# mcu_and_input_power.net
KiCad netlist of a schematic drawn in Altium Designer
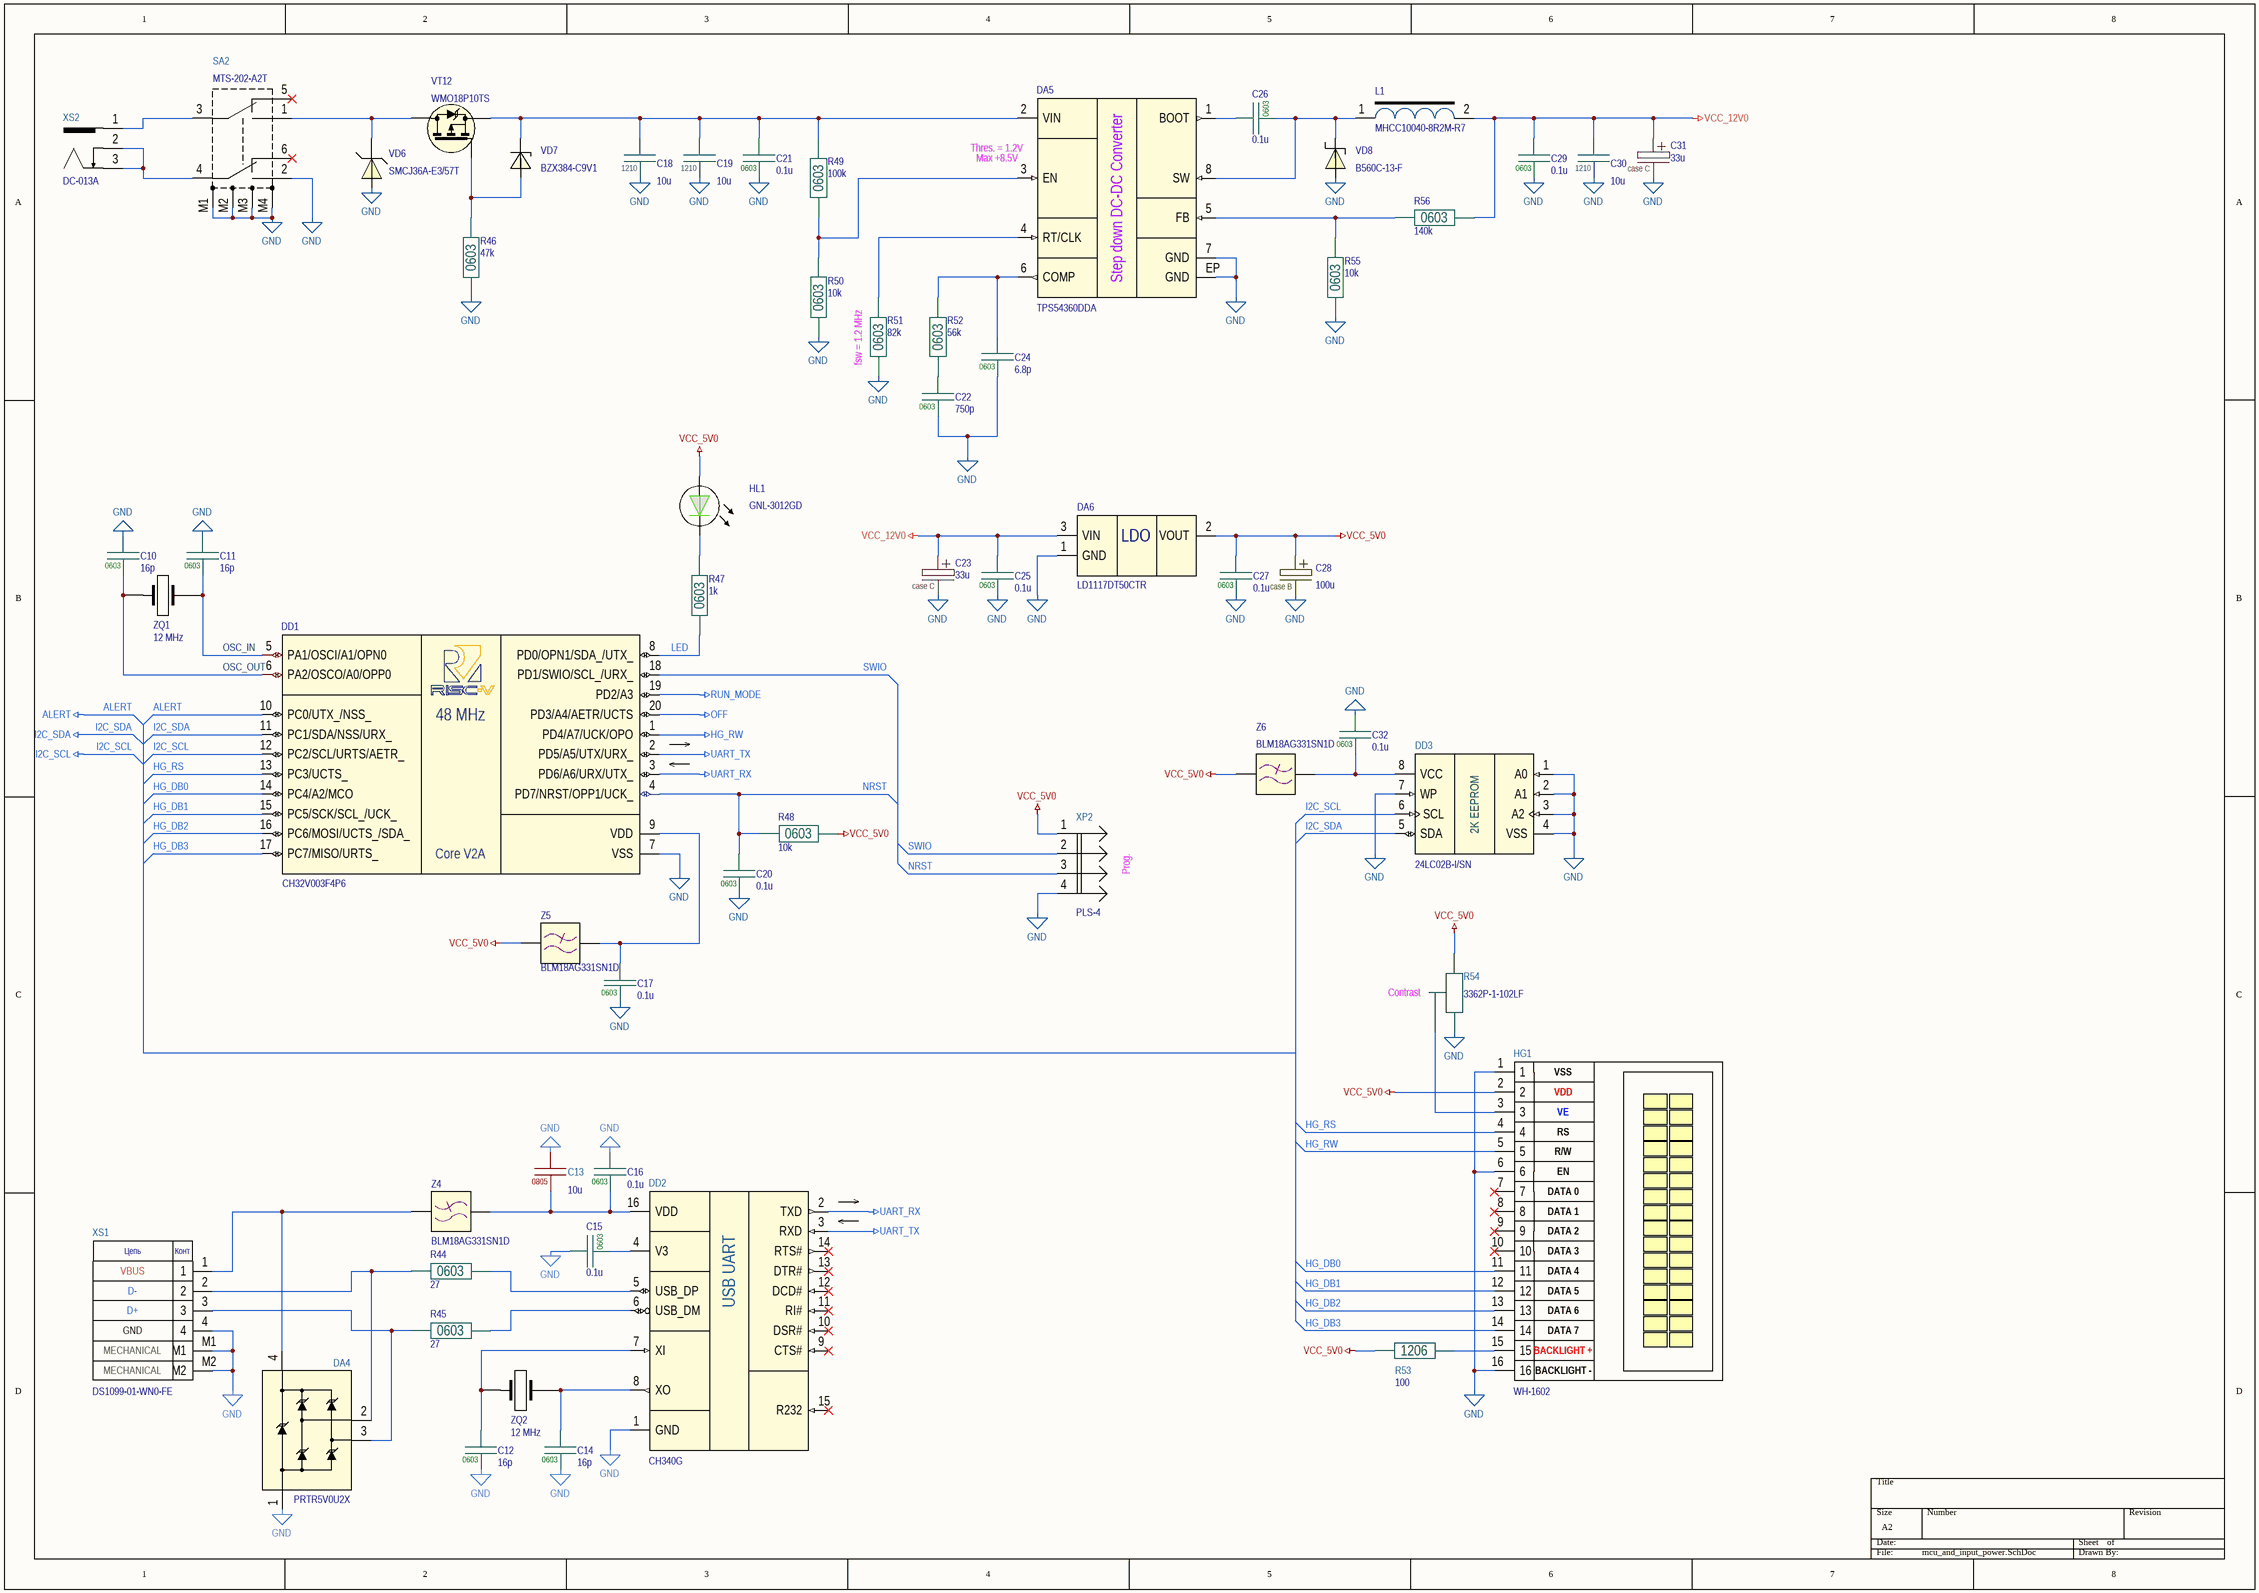
[diagram p0: mcu_and_input_power.SchDoc]

(export (version "E")
  (design (tool "Eeschema 10.0.6"))
  (components
    (comp (ref "C10")
      (value "16p")
      (footprint "PcbLib_RC:CAP0603")
      (description "Capacitors 0603 package case")
      (fields
        (field (name "TOLERANCE") "± 5 %")
        (field (name "VOLTAGE") "50V")
        (field (name "PACKAGE") "0603")
      )
      (libsource (lib "Schlib_RC") (part "C0603"))
    )
    (comp (ref "C11")
      (value "16p")
      (footprint "PcbLib_RC:CAP0603")
      (description "Capacitors 0603 package case")
      (fields
        (field (name "TOLERANCE") "± 5 %")
        (field (name "VOLTAGE") "50V")
        (field (name "PACKAGE") "0603")
      )
      (libsource (lib "Schlib_RC") (part "C0603"))
    )
    (comp (ref "C12")
      (value "16p")
      (footprint "PcbLib_RC:CAP0603")
      (description "Capacitors 0603 package case")
      (fields
        (field (name "TOLERANCE") "± 5 %")
        (field (name "VOLTAGE") "50V")
        (field (name "PACKAGE") "0603")
      )
      (libsource (lib "Schlib_RC") (part "C0603"))
    )
    (comp (ref "C13")
      (value "10u")
      (footprint "PcbLib_RC:CAP0805-0.75")
      (description "Capacitors 0805 package case")
      (fields
        (field (name "TOLERANCE") "± 10 %")
        (field (name "VOLTAGE") "16V")
        (field (name "PACKAGE") "0805")
      )
      (libsource (lib "Schlib_RC") (part "C0805"))
    )
    (comp (ref "C14")
      (value "16p")
      (footprint "PcbLib_RC:CAP0603")
      (description "Capacitors 0603 package case")
      (fields
        (field (name "TOLERANCE") "± 5 %")
        (field (name "VOLTAGE") "50V")
        (field (name "PACKAGE") "0603")
      )
      (libsource (lib "Schlib_RC") (part "C0603"))
    )
    (comp (ref "C15")
      (value "0.1u")
      (footprint "PcbLib_RC:CAP0603")
      (description "Capacitors 0603 package case")
      (fields
        (field (name "TOLERANCE") "± 10 %")
        (field (name "VOLTAGE") "50V")
        (field (name "PACKAGE") "0603")
      )
      (libsource (lib "Schlib_RC") (part "C0603"))
    )
    (comp (ref "C16")
      (value "0.1u")
      (footprint "PcbLib_RC:CAP0603")
      (description "Capacitors 0603 package case")
      (fields
        (field (name "TOLERANCE") "± 10 %")
        (field (name "VOLTAGE") "50V")
        (field (name "PACKAGE") "0603")
      )
      (libsource (lib "Schlib_RC") (part "C0603"))
    )
    (comp (ref "C17")
      (value "0.1u")
      (footprint "PcbLib_RC:CAP0603")
      (description "Capacitors 0603 package case")
      (fields
        (field (name "TOLERANCE") "± 10 %")
        (field (name "VOLTAGE") "50V")
        (field (name "PACKAGE") "0603")
      )
      (libsource (lib "Schlib_RC") (part "C0603"))
    )
    (comp (ref "C18")
      (value "10u")
      (footprint "PcbLib_RC:CAP1210-2.2")
      (description "Capacitors 1210 package case")
      (fields
        (field (name "TOLERANCE") "± 10 %")
        (field (name "VOLTAGE") "100V")
        (field (name "PACKAGE") "1210")
      )
      (libsource (lib "Schlib_RC") (part "C1210"))
    )
    (comp (ref "C19")
      (value "10u")
      (footprint "PcbLib_RC:CAP1210-2.2")
      (description "Capacitors 1210 package case")
      (fields
        (field (name "TOLERANCE") "± 10 %")
        (field (name "VOLTAGE") "100V")
        (field (name "PACKAGE") "1210")
      )
      (libsource (lib "Schlib_RC") (part "C1210"))
    )
    (comp (ref "C20")
      (value "0.1u")
      (footprint "PcbLib_RC:CAP0603")
      (description "Capacitors 0603 package case")
      (fields
        (field (name "TOLERANCE") "± 10 %")
        (field (name "VOLTAGE") "50V")
        (field (name "PACKAGE") "0603")
      )
      (libsource (lib "Schlib_RC") (part "C0603"))
    )
    (comp (ref "C21")
      (value "0.1u")
      (footprint "PcbLib_RC:CAP0603")
      (description "Capacitors 0603 package case")
      (fields
        (field (name "TOLERANCE") "± 10 %")
        (field (name "VOLTAGE") "50V")
        (field (name "PACKAGE") "0603")
      )
      (libsource (lib "Schlib_RC") (part "C0603"))
    )
    (comp (ref "C22")
      (value "750p")
      (footprint "PcbLib_RC:CAP0603")
      (description "Capacitors 0603 package case")
      (fields
        (field (name "TOLERANCE") "± 5 %")
        (field (name "VOLTAGE") "50V")
        (field (name "PACKAGE") "0603")
      )
      (libsource (lib "Schlib_RC") (part "C0603"))
    )
    (comp (ref "C23")
      (value "33u")
      (footprint "PcbLib_RC:CAP_CASE_C")
      (description "Tantalum capacitors case C")
      (fields
        (field (name "TOLERANCE") "± 10 %")
        (field (name "PART NUMBER") "293D336X9020C2TE3")
        (field (name "PACKAGE") "case C")
      )
      (libsource (lib "Schlib_RC") (part "C_CASEC"))
    )
    (comp (ref "C24")
      (value "6.8p")
      (footprint "PcbLib_RC:CAP0603")
      (description "Capacitors 0603 package case")
      (fields
        (field (name "TOLERANCE") "± 0.25 pF")
        (field (name "VOLTAGE") "50V")
        (field (name "PACKAGE") "0603")
      )
      (libsource (lib "Schlib_RC") (part "C0603"))
    )
    (comp (ref "C25")
      (value "0.1u")
      (footprint "PcbLib_RC:CAP0603")
      (description "Capacitors 0603 package case")
      (fields
        (field (name "TOLERANCE") "± 10 %")
        (field (name "VOLTAGE") "50V")
        (field (name "PACKAGE") "0603")
      )
      (libsource (lib "Schlib_RC") (part "C0603"))
    )
    (comp (ref "C26")
      (value "0.1u")
      (footprint "PcbLib_RC:CAP0603")
      (description "Capacitors 0603 package case")
      (fields
        (field (name "TOLERANCE") "± 10 %")
        (field (name "VOLTAGE") "50V")
        (field (name "PACKAGE") "0603")
      )
      (libsource (lib "Schlib_RC") (part "C0603"))
    )
    (comp (ref "C27")
      (value "0.1u")
      (footprint "PcbLib_RC:CAP0603")
      (description "Capacitors 0603 package case")
      (fields
        (field (name "TOLERANCE") "± 10 %")
        (field (name "VOLTAGE") "50V")
        (field (name "PACKAGE") "0603")
      )
      (libsource (lib "Schlib_RC") (part "C0603"))
    )
    (comp (ref "C28")
      (value "100u")
      (footprint "PcbLib_RC:CAP_CASE_B")
      (description "Tantalum capacitors case B")
      (fields
        (field (name "TOLERANCE") "± 10 %")
        (field (name "PART NUMBER") "293D107X0010B2TE3")
        (field (name "PACKAGE") "case B")
      )
      (libsource (lib "Schlib_RC") (part "C_CASEB"))
    )
    (comp (ref "C29")
      (value "0.1u")
      (footprint "PcbLib_RC:CAP0603")
      (description "Capacitors 0603 package case")
      (fields
        (field (name "TOLERANCE") "± 10 %")
        (field (name "VOLTAGE") "50V")
        (field (name "PACKAGE") "0603")
      )
      (libsource (lib "Schlib_RC") (part "C0603"))
    )
    (comp (ref "C30")
      (value "10u")
      (footprint "PcbLib_RC:CAP1210-2.2")
      (description "Capacitors 1210 package case")
      (fields
        (field (name "TOLERANCE") "± 10 %")
        (field (name "VOLTAGE") "100V")
        (field (name "PACKAGE") "1210")
      )
      (libsource (lib "Schlib_RC") (part "C1210"))
    )
    (comp (ref "C31")
      (value "33u")
      (footprint "PcbLib_RC:CAP_CASE_C")
      (description "Tantalum capacitors case C")
      (fields
        (field (name "TOLERANCE") "± 10 %")
        (field (name "PART NUMBER") "293D336X9020C2TE3")
        (field (name "PACKAGE") "case C")
      )
      (libsource (lib "Schlib_RC") (part "C_CASEC"))
    )
    (comp (ref "C32")
      (value "0.1u")
      (footprint "PcbLib_RC:CAP0603")
      (description "Capacitors 0603 package case")
      (fields
        (field (name "TOLERANCE") "± 10 %")
        (field (name "VOLTAGE") "50V")
        (field (name "PACKAGE") "0603")
      )
      (libsource (lib "Schlib_RC") (part "C0603"))
    )
    (comp (ref "DA4")
      (value "PRTR5V0U2X")
      (footprint "PcbLib_ICs:SOT143")
      (description "Ultra low capacitance double rail-to-rail ESD protection diode")
      (fields (field (name "MANUFACTURER") "NXP USA Inc."))
      (libsource (lib "Schlib_NXP_Semiconductors") (part "PRTR5V0U2X"))
    )
    (comp (ref "DA5")
      (value "TPS54360DDA")
      (footprint "PcbLib_ICs:SOIC-8EP")
      (description "60-V Input, 3.5-A, Step-Down DC/DC Converter With Eco-Mode")
      (fields (field (name "MANUFACTURER") "Texas Instruments"))
      (libsource (lib "Schlib_Texas_Instruments") (part "TPS54360DDA"))
    )
    (comp (ref "DA6")
      (value "LD1117DT50CTR")
      (footprint "PcbLib_ICs:TO-252-3")
      (description "Low drop positive voltage regulator")
      (fields (field (name "MANUFACTURER") "STMicroelectronics"))
      (libsource (lib "Schlib_STMicroelectronics") (part "LD1117DT50CTR"))
    )
    (comp (ref "DD1")
      (value "CH32V003F4P6")
      (footprint "PcbLib_ICs:TSSOP-20")
      (description "RISC-V MCU 48MHz with 16KB flash, 2KB RAM")
      (fields (field (name "MANUFACTURER") "WinChipHead"))
      (libsource (lib "Schlib_WCH") (part "CH32V003F4P6"))
    )
    (comp (ref "DD2")
      (value "CH340G")
      (footprint "PcbLib_ICs:SOIC-16")
      (description "USB to Serial Port Chip")
      (fields (field (name "MANUFACTURER") "WinChipHead"))
      (libsource (lib "Schlib_WCH") (part "CH340G"))
    )
    (comp (ref "DD3")
      (value "24LC02B-I/SN")
      (footprint "PcbLib_ICs:SOIC-8")
      (description "2K I2C Serial EEPROM")
      (fields (field (name "MANUFACTURER") "Microchip Technology"))
      (libsource (lib "Schlib_Microchip") (part "24LC02B-I/SN"))
    )
    (comp (ref "HG1")
      (value "WH-1602")
      (footprint "PcbLib_Others:WH1602")
      (description "1602 Display with 16 pin PBS connector")
      (libsource (lib "Schlib_OtherComponents") (part "WH-1602"))
    )
    (comp (ref "HL1")
      (value "GNL-3012GD")
      (footprint "PcbLib_Discrete:GNL-3012GD")
      (description "Standard Brightness 3mm LED")
      (fields (field (name "MANUFACTURER") "G-Nor Optoelectronics"))
      (libsource (lib "Schlib_OtherComponents") (part "GNL-3012GD"))
    )
    (comp (ref "L1")
      (value "MHCC10040-8R2M-R7")
      (footprint "PcbLib_RC:MHCC10040")
      (description "Shielded SMD Power Inductor")
      (fields (field (name "MANUFACTURER") "Chilisin Elec"))
      (libsource (lib "Schlib_OtherComponents") (part "MHCC10040-8R2M-R7"))
    )
    (comp (ref "R44")
      (value "27")
      (footprint "PcbLib_RC:RES0603B")
      (description "Resistor 0603 package case")
      (fields
        (field (name "TOLERANCE") "± 1 %")
        (field (name "PART NUMBER") "RC0603FR-0727RL")
        (field (name "PACKAGE") "0603")
      )
      (libsource (lib "Schlib_RC") (part "R0603"))
    )
    (comp (ref "R45")
      (value "27")
      (footprint "PcbLib_RC:RES0603B")
      (description "Resistor 0603 package case")
      (fields
        (field (name "TOLERANCE") "± 1 %")
        (field (name "PART NUMBER") "RC0603FR-0727RL")
        (field (name "PACKAGE") "0603")
      )
      (libsource (lib "Schlib_RC") (part "R0603"))
    )
    (comp (ref "R46")
      (value "47k")
      (footprint "PcbLib_RC:RES0603B")
      (description "Resistor 0603 package case")
      (fields
        (field (name "TOLERANCE") "± 1 %")
        (field (name "PART NUMBER") "RC0603FR-0747KL")
        (field (name "PACKAGE") "0603")
      )
      (libsource (lib "Schlib_RC") (part "R0603"))
    )
    (comp (ref "R47")
      (value "1k")
      (footprint "PcbLib_RC:RES0603B")
      (description "Resistor 0603 package case")
      (fields
        (field (name "TOLERANCE") "± 1 %")
        (field (name "PART NUMBER") "RC0603FR-071KL")
        (field (name "PACKAGE") "0603")
      )
      (libsource (lib "Schlib_RC") (part "R0603"))
    )
    (comp (ref "R48")
      (value "10k")
      (footprint "PcbLib_RC:RES0603B")
      (description "Resistor 0603 package case")
      (fields
        (field (name "TOLERANCE") "± 1 %")
        (field (name "PART NUMBER") "RC0603FR-0710KL")
        (field (name "PACKAGE") "0603")
      )
      (libsource (lib "Schlib_RC") (part "R0603"))
    )
    (comp (ref "R49")
      (value "100k")
      (footprint "PcbLib_RC:RES0603B")
      (description "Resistor 0603 package case")
      (fields
        (field (name "TOLERANCE") "± 1 %")
        (field (name "PART NUMBER") "RC0603FR-07100KL")
        (field (name "PACKAGE") "0603")
      )
      (libsource (lib "Schlib_RC") (part "R0603"))
    )
    (comp (ref "R50")
      (value "10k")
      (footprint "PcbLib_RC:RES0603B")
      (description "Resistor 0603 package case")
      (fields
        (field (name "TOLERANCE") "± 1 %")
        (field (name "PART NUMBER") "RC0603FR-0710KL")
        (field (name "PACKAGE") "0603")
      )
      (libsource (lib "Schlib_RC") (part "R0603"))
    )
    (comp (ref "R51")
      (value "82k")
      (footprint "PcbLib_RC:RES0603B")
      (description "Resistor 0603 package case")
      (fields
        (field (name "TOLERANCE") "± 1 %")
        (field (name "PART NUMBER") "RC0603FR-0782KL")
        (field (name "PACKAGE") "0603")
      )
      (libsource (lib "Schlib_RC") (part "R0603"))
    )
    (comp (ref "R52")
      (value "56k")
      (footprint "PcbLib_RC:RES0603B")
      (description "Resistor 0603 package case")
      (fields
        (field (name "TOLERANCE") "± 1 %")
        (field (name "PART NUMBER") "RC0603FR-0756KL")
        (field (name "PACKAGE") "0603")
      )
      (libsource (lib "Schlib_RC") (part "R0603"))
    )
    (comp (ref "R53")
      (value "100")
      (footprint "PcbLib_RC:RES1206C")
      (description "Resistor 1206 package case")
      (fields
        (field (name "TOLERANCE") "± 1 %")
        (field (name "MANUFACTURER") "Yageo")
        (field (name "PACKAGE") "1206")
      )
      (libsource (lib "Schlib_RC") (part "R1206"))
    )
    (comp (ref "R54")
      (value "3362P-1-102LF")
      (footprint "PcbLib_Others:3362P")
      (description "TRIMMER 1K OHM 0.5W PC PIN TOP")
      (fields (field (name "MANUFACTURER") "Bourns Inc."))
      (libsource (lib "Schlib_Bourns") (part "3362P-1-102LF"))
    )
    (comp (ref "R55")
      (value "10k")
      (footprint "PcbLib_RC:RES0603B")
      (description "Resistor 0603 package case")
      (fields
        (field (name "TOLERANCE") "± 1 %")
        (field (name "PART NUMBER") "RC0603FR-0710KL")
        (field (name "PACKAGE") "0603")
      )
      (libsource (lib "Schlib_RC") (part "R0603"))
    )
    (comp (ref "R56")
      (value "140k")
      (footprint "PcbLib_RC:RES0603B")
      (description "Resistor 0603 package case")
      (fields
        (field (name "TOLERANCE") "± 1 %")
        (field (name "PART NUMBER") "RC0603FR-07140KL")
        (field (name "PACKAGE") "0603")
      )
      (libsource (lib "Schlib_RC") (part "R0603"))
    )
    (comp (ref "SA2")
      (value "MTS-202-A2T")
      (footprint "PcbLib_Others:MTS-202-A2T")
      (description "Switch")
      (fields (field (name "MANUFACTURER") "RUICHI"))
      (libsource (lib "Schlib_OtherComponents") (part "MTS-202-A2T"))
    )
    (comp (ref "VD6")
      (value "SMCJ36A-E3/57T")
      (footprint "PcbLib_Discrete:DO-214AB")
      (description "36V Transient Voltage Suppressors")
      (fields (field (name "MANUFACTURER") "Vishay"))
      (libsource (lib "Schlib_Vishay") (part "SMCJ36A-E3/57T"))
    )
    (comp (ref "VD7")
      (value "BZX384-C9V1")
      (footprint "PcbLib_Discrete:SOD-323")
      (description "Voltage regulator diodes 9.1V")
      (libsource (lib "Schlib_NXP_Semiconductors") (part "BZX384-C9V1"))
    )
    (comp (ref "VD8")
      (value "B560C-13-F")
      (footprint "PcbLib_Discrete:DO-214AB")
      (description "Diode Schottky 60V, 5A")
      (fields (field (name "MANUFACTURER") "Diodes Incorporated"))
      (libsource (lib "Schlib_Diodes_Incorporated") (part "B560C-13-F"))
    )
    (comp (ref "VT12")
      (value "WMO18P10TS")
      (footprint "PcbLib_ICs:TO-252-3")
      (description "P-Channel MOSFET, -100V, -18A")
      (fields (field (name "MANUFACTURER") "Wayon"))
      (libsource (lib "Schlib_OtherComponents") (part "WMO18P10TS"))
    )
    (comp (ref "XP2")
      (value "PLS-4")
      (footprint "PcbLib_Pin_Headers:PLS-4")
      (libsource (lib "Schlib_Pin_Headers") (part "PLS-4"))
    )
    (comp (ref "XS1")
      (value "DS1099-01-WN0-FE")
      (footprint "PcbLib_Connectors:DS1099-01-WN0-FE")
      (description "USB Type B Vertical Female")
      (fields (field (name "MANUFACTURER") "Connfly"))
      (libsource (lib "Schlib_Connfly") (part "DS1099-01-WN0-FE"))
    )
    (comp (ref "XS2")
      (value "DC-013A")
      (footprint "PcbLib_Others:DC-013A")
      (description "Straight DC Power Receptacle Connector 2mm x 6.4mm")
      (libsource (lib "Schlib_OtherComponents") (part "DC-013A"))
    )
    (comp (ref "Z4")
      (value "BLM18AG331SN1D")
      (footprint "PcbLib_RC:BLM0603P")
      (description "Power line filter, imperdance 330 Ohm (current 05A)")
      (libsource (lib "Schlib_Murata") (part "BLM18AG331SN1D"))
    )
    (comp (ref "Z5")
      (value "BLM18AG331SN1D")
      (footprint "PcbLib_RC:BLM0603P")
      (description "Power line filter, imperdance 330 Ohm (current 05A)")
      (libsource (lib "") (part "BLM18AG331SN1D_1"))
    )
    (comp (ref "Z6")
      (value "BLM18AG331SN1D")
      (footprint "PcbLib_RC:BLM0603P")
      (description "Power line filter, imperdance 330 Ohm (current 05A)")
      (libsource (lib "") (part "BLM18AG331SN1D_1"))
    )
    (comp (ref "ZQ1")
      (value "SJK-6C-12.000-16-30-50-B-50-H")
      (footprint "PcbLib_Others:HC-49/US_With_Hole")
      (description "Crystal resonator")
      (fields (field (name "MANUFACTURER") "SJK") (field (name "FREQUENCY") "12 MHz"))
      (libsource (lib "Schlib_OtherComponents") (part "HC-49"))
    )
    (comp (ref "ZQ2")
      (value "SJK-6C-12.000-16-30-50-B-50-H")
      (footprint "PcbLib_Others:HC-49/US_With_Hole")
      (description "Crystal resonator")
      (fields (field (name "MANUFACTURER") "SJK") (field (name "FREQUENCY") "12 MHz"))
      (libsource (lib "Schlib_OtherComponents") (part "HC-49"))
    )
  )
  (nets
    (net (code "1") (name "/HG_DB0") (class "Default")
      (node (ref "DD1") (pin "14") (pinfunction "PC4/A2/MCO_14") (pintype "bidirectional"))
      (node (ref "HG1") (pin "11") (pinfunction "11_11") (pintype "passive"))
    )
    (net (code "2") (name "/HG_DB1") (class "Default")
      (node (ref "DD1") (pin "15") (pinfunction "PC5/SCK/SCL_/UCK__15") (pintype "bidirectional"))
      (node (ref "HG1") (pin "12") (pinfunction "12_12") (pintype "passive"))
    )
    (net (code "3") (name "/HG_DB2") (class "Default")
      (node (ref "DD1") (pin "16") (pinfunction "PC6/MOSI/UCTS_/SDA__16") (pintype "bidirectional"))
      (node (ref "HG1") (pin "13") (pinfunction "13_13") (pintype "passive"))
    )
    (net (code "4") (name "/HG_DB3") (class "Default")
      (node (ref "DD1") (pin "17") (pinfunction "PC7/MISO/URTS__17") (pintype "bidirectional"))
      (node (ref "HG1") (pin "14") (pinfunction "14_14") (pintype "passive"))
    )
    (net (code "5") (name "/HG_RS") (class "Default")
      (node (ref "DD1") (pin "13") (pinfunction "PC3/UCTS__13") (pintype "bidirectional"))
      (node (ref "HG1") (pin "4") (pinfunction "4_4") (pintype "passive"))
    )
    (net (code "6") (name "/LED") (class "Default")
      (node (ref "DD1") (pin "8") (pinfunction "PD0/OPN1/SDA_/UTX__8") (pintype "bidirectional"))
      (node (ref "R47") (pin "1") (pinfunction "1_1") (pintype "passive"))
    )
    (net (code "7") (name "/NRST") (class "Default")
      (node (ref "C20") (pin "2") (pinfunction "2_2") (pintype "passive"))
      (node (ref "DD1") (pin "4") (pinfunction "PD7/NRST/OPP1/UCK__4") (pintype "bidirectional"))
      (node (ref "R48") (pin "1") (pinfunction "1_1") (pintype "passive"))
      (node (ref "XP2") (pin "3") (pinfunction "3_3") (pintype "passive"))
    )
    (net (code "8") (name "/OSC_IN") (class "Default")
      (node (ref "C11") (pin "1") (pinfunction "1_1") (pintype "passive"))
      (node (ref "DD1") (pin "5") (pinfunction "PA1/OSCI/A1/OPN0_5") (pintype "bidirectional"))
      (node (ref "ZQ1") (pin "2") (pinfunction "XTAL1_2") (pintype "passive"))
    )
    (net (code "9") (name "/OSC_OUT") (class "Default")
      (node (ref "C10") (pin "1") (pinfunction "1_1") (pintype "passive"))
      (node (ref "DD1") (pin "6") (pinfunction "PA2/OSCO/A0/OPP0_6") (pintype "bidirectional"))
      (node (ref "ZQ1") (pin "1") (pinfunction "XTAL0_1") (pintype "passive"))
    )
    (net (code "10") (name "/SWIO") (class "Default")
      (node (ref "DD1") (pin "18") (pinfunction "PD1/SWIO/SCL_/URX__18") (pintype "bidirectional"))
      (node (ref "XP2") (pin "2") (pinfunction "2_2") (pintype "passive"))
    )
    (net (code "11") (name "ALERT") (class "Default")
      (node (ref "DD1") (pin "10") (pinfunction "PC0/UTX_/NSS__10") (pintype "bidirectional"))
    )
    (net (code "12") (name "GND") (class "Default")
      (node (ref "C10") (pin "2") (pinfunction "2_2") (pintype "passive"))
      (node (ref "C11") (pin "2") (pinfunction "2_2") (pintype "passive"))
      (node (ref "C12") (pin "1") (pinfunction "1_1") (pintype "passive"))
      (node (ref "C13") (pin "2") (pinfunction "2_2") (pintype "passive"))
      (node (ref "C14") (pin "1") (pinfunction "1_1") (pintype "passive"))
      (node (ref "C15") (pin "2") (pinfunction "2_2") (pintype "passive"))
      (node (ref "C16") (pin "2") (pinfunction "2_2") (pintype "passive"))
      (node (ref "C17") (pin "1") (pinfunction "1_1") (pintype "passive"))
      (node (ref "C18") (pin "1") (pinfunction "1_1") (pintype "passive"))
      (node (ref "C19") (pin "1") (pinfunction "1_1") (pintype "passive"))
      (node (ref "C20") (pin "1") (pinfunction "1_1") (pintype "passive"))
      (node (ref "C21") (pin "1") (pinfunction "1_1") (pintype "passive"))
      (node (ref "C22") (pin "1") (pinfunction "1_1") (pintype "passive"))
      (node (ref "C23") (pin "2") (pinfunction "2_2") (pintype "passive"))
      (node (ref "C24") (pin "1") (pinfunction "1_1") (pintype "passive"))
      (node (ref "C25") (pin "1") (pinfunction "1_1") (pintype "passive"))
      (node (ref "C27") (pin "1") (pinfunction "1_1") (pintype "passive"))
      (node (ref "C28") (pin "2") (pinfunction "2_2") (pintype "passive"))
      (node (ref "C29") (pin "1") (pinfunction "1_1") (pintype "passive"))
      (node (ref "C30") (pin "1") (pinfunction "1_1") (pintype "passive"))
      (node (ref "C31") (pin "2") (pinfunction "2_2") (pintype "passive"))
      (node (ref "C32") (pin "2") (pinfunction "2_2") (pintype "passive"))
      (node (ref "DA4") (pin "1") (pinfunction "GND_1") (pintype "passive"))
      (node (ref "DA5") (pin "7") (pinfunction "GND_7") (pintype "power_in"))
      (node (ref "DA5") (pin "EP") (pinfunction "GND_EP") (pintype "power_in"))
      (node (ref "DA6") (pin "1") (pinfunction "GND_1") (pintype "power_in"))
      (node (ref "DD1") (pin "7") (pinfunction "VSS_7") (pintype "power_in"))
      (node (ref "DD2") (pin "1") (pinfunction "GND_1") (pintype "power_in"))
      (node (ref "DD3") (pin "1") (pinfunction "A0_1") (pintype "input"))
      (node (ref "DD3") (pin "2") (pinfunction "A1_2") (pintype "input"))
      (node (ref "DD3") (pin "3") (pinfunction "A2_3") (pintype "input"))
      (node (ref "DD3") (pin "4") (pinfunction "VSS_4") (pintype "power_in"))
      (node (ref "DD3") (pin "7") (pinfunction "WP_7") (pintype "input"))
      (node (ref "HG1") (pin "1") (pinfunction "1_1") (pintype "passive"))
      (node (ref "HG1") (pin "16") (pinfunction "16_16") (pintype "passive"))
      (node (ref "HG1") (pin "6") (pinfunction "6_6") (pintype "passive"))
      (node (ref "R46") (pin "1") (pinfunction "1_1") (pintype "passive"))
      (node (ref "R50") (pin "1") (pinfunction "1_1") (pintype "passive"))
      (node (ref "R51") (pin "2") (pinfunction "2_2") (pintype "passive"))
      (node (ref "R54") (pin "3") (pinfunction "3_3") (pintype "passive"))
      (node (ref "R55") (pin "1") (pinfunction "1_1") (pintype "passive"))
      (node (ref "SA2") (pin "2") (pinfunction "2_2") (pintype "passive"))
      (node (ref "SA2") (pin "M1") (pinfunction "M1_M1") (pintype "passive"))
      (node (ref "SA2") (pin "M2") (pinfunction "M2_M2") (pintype "passive"))
      (node (ref "SA2") (pin "M3") (pinfunction "M3_M3") (pintype "passive"))
      (node (ref "SA2") (pin "M4") (pinfunction "M4_M4") (pintype "passive"))
      (node (ref "VD6") (pin "1") (pinfunction "C_1") (pintype "passive"))
      (node (ref "VD8") (pin "1") (pinfunction "A_1") (pintype "passive"))
      (node (ref "XP2") (pin "4") (pinfunction "4_4") (pintype "passive"))
      (node (ref "XS1") (pin "4") (pinfunction "4_4") (pintype "passive"))
      (node (ref "XS1") (pin "M1") (pinfunction "M1_M1") (pintype "passive"))
      (node (ref "XS1") (pin "M2") (pinfunction "M2_M2") (pintype "passive"))
    )
    (net (code "13") (name "HG_RW") (class "Default")
      (node (ref "DD1") (pin "1") (pinfunction "PD4/A7/UCK/OPO_1") (pintype "bidirectional"))
      (node (ref "HG1") (pin "5") (pinfunction "5_5") (pintype "passive"))
    )
    (net (code "14") (name "I2C_SCL") (class "Default")
      (node (ref "DD1") (pin "12") (pinfunction "PC2/SCL/URTS/AETR__12") (pintype "bidirectional"))
      (node (ref "DD3") (pin "6") (pinfunction "SCL_6") (pintype "input"))
    )
    (net (code "15") (name "I2C_SDA") (class "Default")
      (node (ref "DD1") (pin "11") (pinfunction "PC1/SDA/NSS/URX__11") (pintype "bidirectional"))
      (node (ref "DD3") (pin "5") (pinfunction "SDA_5") (pintype "bidirectional"))
    )
    (net (code "16") (name "Net-(C22-Pad2)") (class "Default")
      (node (ref "C22") (pin "2") (pinfunction "2_2") (pintype "passive"))
      (node (ref "R52") (pin "2") (pinfunction "2_2") (pintype "passive"))
    )
    (net (code "17") (name "Net-(DA4-IO1)") (class "Default")
      (node (ref "DA4") (pin "2") (pinfunction "IO1_2") (pintype "passive"))
      (node (ref "R44") (pin "1") (pinfunction "1_1") (pintype "passive"))
      (node (ref "XS1") (pin "2") (pinfunction "2_2") (pintype "passive"))
    )
    (net (code "18") (name "Net-(DA4-IO2)") (class "Default")
      (node (ref "DA4") (pin "3") (pinfunction "IO2_3") (pintype "passive"))
      (node (ref "R45") (pin "1") (pinfunction "1_1") (pintype "passive"))
      (node (ref "XS1") (pin "3") (pinfunction "3_3") (pintype "passive"))
    )
    (net (code "19") (name "Net-(DA4-VCC)") (class "Default")
      (node (ref "DA4") (pin "4") (pinfunction "VCC_4") (pintype "passive"))
      (node (ref "XS1") (pin "1") (pinfunction "1_1") (pintype "passive"))
      (node (ref "Z4") (pin "1") (pinfunction "1_1") (pintype "passive"))
    )
    (net (code "20") (name "Net-(DA5-BOOT)") (class "Default")
      (node (ref "C26") (pin "2") (pinfunction "2_2") (pintype "passive"))
      (node (ref "DA5") (pin "1") (pinfunction "BOOT_1") (pintype "output"))
    )
    (net (code "21") (name "Net-(DA5-COMP)") (class "Default")
      (node (ref "C24") (pin "2") (pinfunction "2_2") (pintype "passive"))
      (node (ref "DA5") (pin "6") (pinfunction "COMP_6") (pintype "output"))
      (node (ref "R52") (pin "1") (pinfunction "1_1") (pintype "passive"))
    )
    (net (code "22") (name "Net-(DA5-EN)") (class "Default")
      (node (ref "DA5") (pin "3") (pinfunction "EN_3") (pintype "input"))
      (node (ref "R49") (pin "2") (pinfunction "2_2") (pintype "passive"))
      (node (ref "R50") (pin "2") (pinfunction "2_2") (pintype "passive"))
    )
    (net (code "23") (name "Net-(DA5-FB)") (class "Default")
      (node (ref "DA5") (pin "5") (pinfunction "FB_5") (pintype "input"))
      (node (ref "R55") (pin "2") (pinfunction "2_2") (pintype "passive"))
      (node (ref "R56") (pin "1") (pinfunction "1_1") (pintype "passive"))
    )
    (net (code "24") (name "Net-(DA5-RT{slash}CLK)") (class "Default")
      (node (ref "DA5") (pin "4") (pinfunction "RT/CLK_4") (pintype "input"))
      (node (ref "R51") (pin "1") (pinfunction "1_1") (pintype "passive"))
    )
    (net (code "25") (name "Net-(DA5-SW)") (class "Default")
      (node (ref "C26") (pin "1") (pinfunction "1_1") (pintype "passive"))
      (node (ref "DA5") (pin "8") (pinfunction "SW_8") (pintype "input"))
      (node (ref "L1") (pin "1") (pinfunction "1_1") (pintype "passive"))
      (node (ref "VD8") (pin "2") (pinfunction "C_2") (pintype "passive"))
    )
    (net (code "26") (name "Net-(DA5-VIN)") (class "Default")
      (node (ref "C18") (pin "2") (pinfunction "2_2") (pintype "passive"))
      (node (ref "C19") (pin "2") (pinfunction "2_2") (pintype "passive"))
      (node (ref "C21") (pin "2") (pinfunction "2_2") (pintype "passive"))
      (node (ref "DA5") (pin "2") (pinfunction "VIN_2") (pintype "power_in"))
      (node (ref "R49") (pin "1") (pinfunction "1_1") (pintype "passive"))
      (node (ref "VD7") (pin "1") (pinfunction "1_1") (pintype "passive"))
      (node (ref "VT12") (pin "3") (pinfunction "S_3") (pintype "passive"))
    )
    (net (code "27") (name "Net-(DD1-VDD)") (class "Default")
      (node (ref "C17") (pin "2") (pinfunction "2_2") (pintype "passive"))
      (node (ref "DD1") (pin "9") (pinfunction "VDD_9") (pintype "power_in"))
      (node (ref "Z5") (pin "1") (pinfunction "1_1") (pintype "passive"))
    )
    (net (code "28") (name "Net-(DD2-USB_DM)") (class "Default")
      (node (ref "DD2") (pin "6") (pinfunction "USB_DM_6") (pintype "bidirectional"))
      (node (ref "R45") (pin "2") (pinfunction "2_2") (pintype "passive"))
    )
    (net (code "29") (name "Net-(DD2-USB_DP)") (class "Default")
      (node (ref "DD2") (pin "5") (pinfunction "USB_DP_5") (pintype "bidirectional"))
      (node (ref "R44") (pin "2") (pinfunction "2_2") (pintype "passive"))
    )
    (net (code "30") (name "Net-(DD2-V3)") (class "Default")
      (node (ref "C15") (pin "1") (pinfunction "1_1") (pintype "passive"))
      (node (ref "DD2") (pin "4") (pinfunction "V3_4") (pintype "power_in"))
    )
    (net (code "31") (name "Net-(DD2-VDD)") (class "Default")
      (node (ref "C13") (pin "1") (pinfunction "1_1") (pintype "passive"))
      (node (ref "C16") (pin "1") (pinfunction "1_1") (pintype "passive"))
      (node (ref "DD2") (pin "16") (pinfunction "VDD_16") (pintype "power_in"))
      (node (ref "Z4") (pin "2") (pinfunction "2_2") (pintype "passive"))
    )
    (net (code "32") (name "Net-(DD2-XI)") (class "Default")
      (node (ref "C12") (pin "2") (pinfunction "2_2") (pintype "passive"))
      (node (ref "DD2") (pin "7") (pinfunction "XI_7") (pintype "input"))
      (node (ref "ZQ2") (pin "1") (pinfunction "XTAL0_1") (pintype "passive"))
    )
    (net (code "33") (name "Net-(DD2-XO)") (class "Default")
      (node (ref "C14") (pin "2") (pinfunction "2_2") (pintype "passive"))
      (node (ref "DD2") (pin "8") (pinfunction "XO_8") (pintype "output"))
      (node (ref "ZQ2") (pin "2") (pinfunction "XTAL1_2") (pintype "passive"))
    )
    (net (code "34") (name "Net-(DD3-VCC)") (class "Default")
      (node (ref "C32") (pin "1") (pinfunction "1_1") (pintype "passive"))
      (node (ref "DD3") (pin "8") (pinfunction "VCC_8") (pintype "power_in"))
      (node (ref "Z6") (pin "1") (pinfunction "1_1") (pintype "passive"))
    )
    (net (code "35") (name "Net-(HG1-Pad3)") (class "Default")
      (node (ref "HG1") (pin "3") (pinfunction "3_3") (pintype "passive"))
      (node (ref "R54") (pin "2") (pinfunction "2_2") (pintype "passive"))
    )
    (net (code "36") (name "Net-(HG1-Pad15)") (class "Default")
      (node (ref "HG1") (pin "15") (pinfunction "15_15") (pintype "passive"))
      (node (ref "R53") (pin "2") (pinfunction "2_2") (pintype "passive"))
    )
    (net (code "37") (name "Net-(HL1-Pad1)") (class "Default")
      (node (ref "HL1") (pin "1") (pinfunction "1_1") (pintype "passive"))
      (node (ref "R47") (pin "2") (pinfunction "2_2") (pintype "passive"))
    )
    (net (code "38") (name "Net-(SA2-Pad3)") (class "Default")
      (node (ref "SA2") (pin "3") (pinfunction "3_3") (pintype "passive"))
      (node (ref "XS2") (pin "1") (pinfunction "1_1") (pintype "passive"))
    )
    (net (code "39") (name "Net-(SA2-Pad4)") (class "Default")
      (node (ref "SA2") (pin "4") (pinfunction "4_4") (pintype "passive"))
      (node (ref "XS2") (pin "2") (pinfunction "2_2") (pintype "passive"))
      (node (ref "XS2") (pin "3") (pinfunction "3_3") (pintype "passive"))
    )
    (net (code "40") (name "Net-(VD6-A)") (class "Default")
      (node (ref "SA2") (pin "1") (pinfunction "1_1") (pintype "passive"))
      (node (ref "VD6") (pin "2") (pinfunction "A_2") (pintype "passive"))
      (node (ref "VT12") (pin "2") (pinfunction "D_2") (pintype "passive"))
    )
    (net (code "41") (name "Net-(VT12-G)") (class "Default")
      (node (ref "R46") (pin "2") (pinfunction "2_2") (pintype "passive"))
      (node (ref "VD7") (pin "2") (pinfunction "2_2") (pintype "passive"))
      (node (ref "VT12") (pin "1") (pinfunction "G_1") (pintype "passive"))
    )
    (net (code "42") (name "OFF") (class "Default")
      (node (ref "DD1") (pin "20") (pinfunction "PD3/A4/AETR/UCTS_20") (pintype "bidirectional"))
    )
    (net (code "43") (name "RUN_MODE") (class "Default")
      (node (ref "DD1") (pin "19") (pinfunction "PD2/A3_19") (pintype "bidirectional"))
    )
    (net (code "44") (name "UART_RX") (class "Default")
      (node (ref "DD1") (pin "3") (pinfunction "PD6/A6/URX/UTX__3") (pintype "bidirectional"))
      (node (ref "DD2") (pin "2") (pinfunction "TXD_2") (pintype "output"))
    )
    (net (code "45") (name "UART_TX") (class "Default")
      (node (ref "DD1") (pin "2") (pinfunction "PD5/A5/UTX/URX__2") (pintype "bidirectional"))
      (node (ref "DD2") (pin "3") (pinfunction "RXD_3") (pintype "input"))
    )
    (net (code "46") (name "VCC_5V0") (class "Default")
      (node (ref "C27") (pin "2") (pinfunction "2_2") (pintype "passive"))
      (node (ref "C28") (pin "1") (pinfunction "1_1") (pintype "passive"))
      (node (ref "DA6") (pin "2") (pinfunction "VOUT_2") (pintype "power_in"))
      (node (ref "HG1") (pin "2") (pinfunction "2_2") (pintype "passive"))
      (node (ref "HL1") (pin "2") (pinfunction "2_2") (pintype "passive"))
      (node (ref "R48") (pin "2") (pinfunction "2_2") (pintype "passive"))
      (node (ref "R53") (pin "1") (pinfunction "1_1") (pintype "passive"))
      (node (ref "R54") (pin "1") (pinfunction "1_1") (pintype "passive"))
      (node (ref "XP2") (pin "1") (pinfunction "1_1") (pintype "passive"))
      (node (ref "Z5") (pin "2") (pinfunction "2_2") (pintype "passive"))
      (node (ref "Z6") (pin "2") (pinfunction "2_2") (pintype "passive"))
    )
    (net (code "47") (name "VCC_12V0") (class "Default")
      (node (ref "C23") (pin "1") (pinfunction "1_1") (pintype "passive"))
      (node (ref "C25") (pin "2") (pinfunction "2_2") (pintype "passive"))
      (node (ref "C29") (pin "2") (pinfunction "2_2") (pintype "passive"))
      (node (ref "C30") (pin "2") (pinfunction "2_2") (pintype "passive"))
      (node (ref "C31") (pin "1") (pinfunction "1_1") (pintype "passive"))
      (node (ref "DA6") (pin "3") (pinfunction "VIN_3") (pintype "power_in"))
      (node (ref "L1") (pin "2") (pinfunction "2_2") (pintype "passive"))
      (node (ref "R56") (pin "2") (pinfunction "2_2") (pintype "passive"))
    )
    (net (code "48") (name "unconnected-(DD2-CTS#-Pad9)") (class "Default")
      (node (ref "DD2") (pin "9") (pinfunction "CTS#_9") (pintype "input+no_connect"))
    )
    (net (code "49") (name "unconnected-(DD2-DCD#-Pad12)") (class "Default")
      (node (ref "DD2") (pin "12") (pinfunction "DCD#_12") (pintype "input+no_connect"))
    )
    (net (code "50") (name "unconnected-(DD2-DSR#-Pad10)") (class "Default")
      (node (ref "DD2") (pin "10") (pinfunction "DSR#_10") (pintype "input+no_connect"))
    )
    (net (code "51") (name "unconnected-(DD2-DTR#-Pad13)") (class "Default")
      (node (ref "DD2") (pin "13") (pinfunction "DTR#_13") (pintype "output+no_connect"))
    )
    (net (code "52") (name "unconnected-(DD2-R232-Pad15)") (class "Default")
      (node (ref "DD2") (pin "15") (pinfunction "R232_15") (pintype "input+no_connect"))
    )
    (net (code "53") (name "unconnected-(DD2-RI#-Pad11)") (class "Default")
      (node (ref "DD2") (pin "11") (pinfunction "RI#_11") (pintype "input+no_connect"))
    )
    (net (code "54") (name "unconnected-(DD2-RTS#-Pad14)") (class "Default")
      (node (ref "DD2") (pin "14") (pinfunction "RTS#_14") (pintype "output+no_connect"))
    )
    (net (code "55") (name "unconnected-(HG1-Pad7)") (class "Default")
      (node (ref "HG1") (pin "7") (pinfunction "7_7") (pintype "passive+no_connect"))
    )
    (net (code "56") (name "unconnected-(HG1-Pad8)") (class "Default")
      (node (ref "HG1") (pin "8") (pinfunction "8_8") (pintype "passive+no_connect"))
    )
    (net (code "57") (name "unconnected-(HG1-Pad9)") (class "Default")
      (node (ref "HG1") (pin "9") (pinfunction "9_9") (pintype "passive+no_connect"))
    )
    (net (code "58") (name "unconnected-(HG1-Pad10)") (class "Default")
      (node (ref "HG1") (pin "10") (pinfunction "10_10") (pintype "passive+no_connect"))
    )
    (net (code "59") (name "unconnected-(SA2-Pad5)") (class "Default")
      (node (ref "SA2") (pin "5") (pinfunction "5_5") (pintype "passive+no_connect"))
    )
    (net (code "60") (name "unconnected-(SA2-Pad6)") (class "Default")
      (node (ref "SA2") (pin "6") (pinfunction "6_6") (pintype "passive+no_connect"))
    )
  )
)
